# Connections.net
KiCad netlist of a schematic drawn in Altium Designer
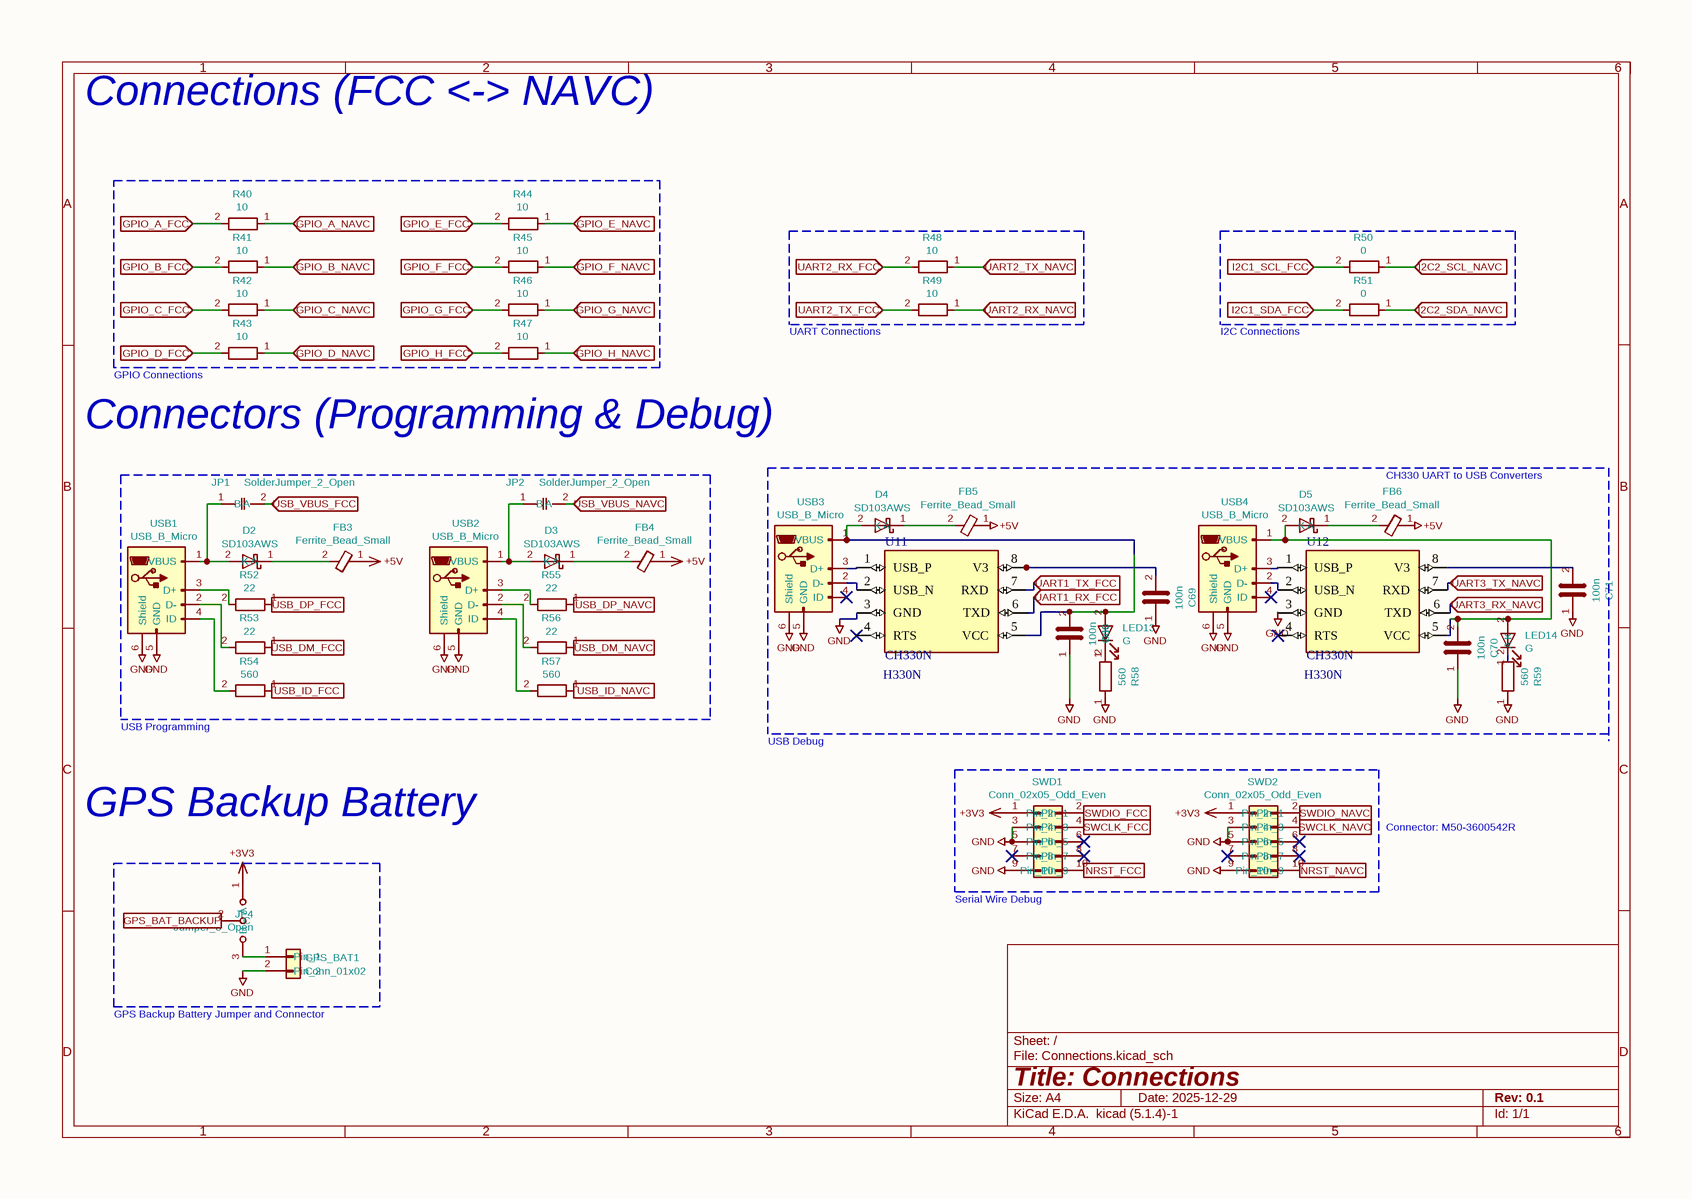
[diagram p0: Connections.SchDoc]

(export (version "E")
  (design (tool "Eeschema 10.0.6"))
  (components
    (comp (ref "C68") (value "100n") (footprint "C_0402_1005Metric") (libsource (lib "Device") (part "C")))
    (comp (ref "C69") (value "100n") (footprint "C_0402_1005Metric") (libsource (lib "Device") (part "C")))
    (comp (ref "C70") (value "100n") (footprint "C_0402_1005Metric") (libsource (lib "Device") (part "C")))
    (comp (ref "C71") (value "100n") (footprint "C_0402_1005Metric") (libsource (lib "Device") (part "C")))
    (comp (ref "D2")
      (value "SD103AWS")
      (footprint "D_SOD-323")
      (libsource (lib "Device") (part "D_Schottky"))
    )
    (comp (ref "D3")
      (value "SD103AWS")
      (footprint "D_SOD-323")
      (libsource (lib "Device") (part "D_Schottky"))
    )
    (comp (ref "D4")
      (value "SD103AWS")
      (footprint "D_SOD-323")
      (libsource (lib "Device") (part "D_Schottky"))
    )
    (comp (ref "D5")
      (value "SD103AWS")
      (footprint "D_SOD-323")
      (libsource (lib "Device") (part "D_Schottky"))
    )
    (comp (ref "FB3")
      (value "Ferrite_Bead_Small")
      (footprint "L_0402_1005Metric")
      (libsource (lib "Hades-rescue") (part "Ferrite_Bead_Small-Device"))
    )
    (comp (ref "FB4")
      (value "Ferrite_Bead_Small")
      (footprint "L_0402_1005Metric")
      (libsource (lib "Hades-rescue") (part "Ferrite_Bead_Small-Device"))
    )
    (comp (ref "FB5")
      (value "Ferrite_Bead_Small")
      (footprint "L_0402_1005Metric")
      (libsource (lib "Hades-rescue") (part "Ferrite_Bead_Small-Device"))
    )
    (comp (ref "FB6")
      (value "Ferrite_Bead_Small")
      (footprint "L_0402_1005Metric")
      (libsource (lib "Hades-rescue") (part "Ferrite_Bead_Small-Device"))
    )
    (comp (ref "GPS_BAT1")
      (value "Conn_01x02")
      (footprint "Molex_PicoBlade_53048-0210_1x02_P1.25mm_Horizontal")
      (libsource (lib "Connector_Generic") (part "Conn_01x02"))
    )
    (comp (ref "JP1")
      (value "SolderJumper_2_Open")
      (footprint "SolderJumper-2_P1.3mm_Open_RoundedPad1.0x1.5mm")
      (libsource (lib "Jumper") (part "SolderJumper_2_Open"))
    )
    (comp (ref "JP2")
      (value "SolderJumper_2_Open")
      (footprint "SolderJumper-2_P1.3mm_Open_RoundedPad1.0x1.5mm")
      (libsource (lib "Jumper") (part "SolderJumper_2_Open"))
    )
    (comp (ref "JP4")
      (value "Jumper_3_Open")
      (footprint "SolderJumper-3_P1.3mm_Open_RoundedPad1.0x1.5mm")
      (libsource (lib "Hades-rescue") (part "Jumper_3_Open-Jumper"))
    )
    (comp (ref "LED13") (value "G") (footprint "LED_0603_1608Metric") (libsource (lib "Device") (part "LED")))
    (comp (ref "LED14") (value "G") (footprint "LED_0603_1608Metric") (libsource (lib "Device") (part "LED")))
    (comp (ref "R40") (value "10") (footprint "R_0402_1005Metric") (libsource (lib "Device") (part "R")))
    (comp (ref "R41") (value "10") (footprint "R_0402_1005Metric") (libsource (lib "Device") (part "R")))
    (comp (ref "R42") (value "10") (footprint "R_0402_1005Metric") (libsource (lib "Device") (part "R")))
    (comp (ref "R43") (value "10") (footprint "R_0402_1005Metric") (libsource (lib "Device") (part "R")))
    (comp (ref "R44") (value "10") (footprint "R_0402_1005Metric") (libsource (lib "Device") (part "R")))
    (comp (ref "R45") (value "10") (footprint "R_0402_1005Metric") (libsource (lib "Device") (part "R")))
    (comp (ref "R46") (value "10") (footprint "R_0402_1005Metric") (libsource (lib "Device") (part "R")))
    (comp (ref "R47") (value "10") (footprint "R_0402_1005Metric") (libsource (lib "Device") (part "R")))
    (comp (ref "R48") (value "10") (footprint "R_0402_1005Metric") (libsource (lib "Device") (part "R")))
    (comp (ref "R49") (value "10") (footprint "R_0402_1005Metric") (libsource (lib "Device") (part "R")))
    (comp (ref "R50") (value "0") (footprint "R_0603_1608Metric") (libsource (lib "Device") (part "R")))
    (comp (ref "R51") (value "0") (footprint "R_0603_1608Metric") (libsource (lib "Device") (part "R")))
    (comp (ref "R52") (value "22") (footprint "R_0402_1005Metric") (libsource (lib "Device") (part "R")))
    (comp (ref "R53") (value "22") (footprint "R_0402_1005Metric") (libsource (lib "Device") (part "R")))
    (comp (ref "R54") (value "560") (footprint "R_0402_1005Metric") (libsource (lib "Device") (part "R")))
    (comp (ref "R55") (value "22") (footprint "R_0402_1005Metric") (libsource (lib "Device") (part "R")))
    (comp (ref "R56") (value "22") (footprint "R_0402_1005Metric") (libsource (lib "Device") (part "R")))
    (comp (ref "R57") (value "560") (footprint "R_0402_1005Metric") (libsource (lib "Device") (part "R")))
    (comp (ref "R58") (value "560") (footprint "R_0603_1608Metric") (libsource (lib "") (part "R_1")))
    (comp (ref "R59") (value "560") (footprint "R_0603_1608Metric") (libsource (lib "") (part "R_1")))
    (comp (ref "SWD1")
      (value "Conn_02x05_Odd_Even")
      (footprint "PinHeader_2x05_P1.27mm_Vertical_SMD")
      (libsource (lib "Connector_Generic") (part "Conn_02x05_Odd_Even"))
    )
    (comp (ref "SWD2")
      (value "Conn_02x05_Odd_Even")
      (footprint "PinHeader_2x05_P1.27mm_Vertical_SMD")
      (libsource (lib "Connector_Generic") (part "Conn_02x05_Odd_Even"))
    )
    (comp (ref "U11")
      (value "H330N")
      (footprint "8-SOIC")
      (description "USB To Serial Chip")
      (fields (field (name "MP") "CH330N") (field (name "MF") "WCH"))
      (libsource (lib "CH330N") (part "CH330N"))
    )
    (comp (ref "U12")
      (value "H330N")
      (footprint "8-SOIC")
      (description "USB To Serial Chip")
      (fields (field (name "MP") "CH330N") (field (name "MF") "WCH"))
      (libsource (lib "CH330N") (part "CH330N"))
    )
    (comp (ref "USB1")
      (value "USB_B_Micro")
      (footprint "USB_Micro-B_Wuerth_629105150521_CircularHoles")
      (libsource (lib "Hades-rescue") (part "USB_B_Micro-Connector"))
    )
    (comp (ref "USB2")
      (value "USB_B_Micro")
      (footprint "USB_Micro-B_Wuerth_629105150521_CircularHoles")
      (libsource (lib "Hades-rescue") (part "USB_B_Micro-Connector"))
    )
    (comp (ref "USB3")
      (value "USB_B_Micro")
      (footprint "USB_Micro-B_Wuerth_629105150521_CircularHoles")
      (libsource (lib "Hades-rescue") (part "USB_B_Micro-Connector"))
    )
    (comp (ref "USB4")
      (value "USB_B_Micro")
      (footprint "USB_Micro-B_Wuerth_629105150521_CircularHoles")
      (libsource (lib "Hades-rescue") (part "USB_B_Micro-Connector"))
    )
  )
  (nets
    (net (code "1") (name "+3V3") (class "Default")
      (node (ref "JP4") (pin "1") (pinfunction "A_1") (pintype "passive"))
      (node (ref "SWD1") (pin "1") (pinfunction "Pin_1_1") (pintype "passive"))
      (node (ref "SWD2") (pin "1") (pinfunction "Pin_1_1") (pintype "passive"))
    )
    (net (code "2") (name "+5V") (class "Default")
      (node (ref "FB3") (pin "1") (pinfunction "1_1") (pintype "passive"))
      (node (ref "FB4") (pin "1") (pinfunction "1_1") (pintype "passive"))
      (node (ref "FB5") (pin "1") (pinfunction "1_1") (pintype "passive"))
      (node (ref "FB6") (pin "1") (pinfunction "1_1") (pintype "passive"))
    )
    (net (code "3") (name "/GPIO_A_FCC") (class "Default")
      (node (ref "R40") (pin "2") (pinfunction "2_2") (pintype "passive"))
    )
    (net (code "4") (name "/GPIO_A_NAVC") (class "Default")
      (node (ref "R40") (pin "1") (pinfunction "1_1") (pintype "passive"))
    )
    (net (code "5") (name "/GPIO_B_FCC") (class "Default")
      (node (ref "R41") (pin "2") (pinfunction "2_2") (pintype "passive"))
    )
    (net (code "6") (name "/GPIO_B_NAVC") (class "Default")
      (node (ref "R41") (pin "1") (pinfunction "1_1") (pintype "passive"))
    )
    (net (code "7") (name "/GPIO_C_FCC") (class "Default")
      (node (ref "R42") (pin "2") (pinfunction "2_2") (pintype "passive"))
    )
    (net (code "8") (name "/GPIO_C_NAVC") (class "Default")
      (node (ref "R42") (pin "1") (pinfunction "1_1") (pintype "passive"))
    )
    (net (code "9") (name "/GPIO_D_FCC") (class "Default")
      (node (ref "R43") (pin "2") (pinfunction "2_2") (pintype "passive"))
    )
    (net (code "10") (name "/GPIO_D_NAVC") (class "Default")
      (node (ref "R43") (pin "1") (pinfunction "1_1") (pintype "passive"))
    )
    (net (code "11") (name "/GPIO_E_FCC") (class "Default")
      (node (ref "R44") (pin "2") (pinfunction "2_2") (pintype "passive"))
    )
    (net (code "12") (name "/GPIO_E_NAVC") (class "Default")
      (node (ref "R44") (pin "1") (pinfunction "1_1") (pintype "passive"))
    )
    (net (code "13") (name "/GPIO_F_FCC") (class "Default")
      (node (ref "R45") (pin "2") (pinfunction "2_2") (pintype "passive"))
    )
    (net (code "14") (name "/GPIO_F_NAVC") (class "Default")
      (node (ref "R45") (pin "1") (pinfunction "1_1") (pintype "passive"))
    )
    (net (code "15") (name "/GPIO_G_FCC") (class "Default")
      (node (ref "R46") (pin "2") (pinfunction "2_2") (pintype "passive"))
    )
    (net (code "16") (name "/GPIO_G_NAVC") (class "Default")
      (node (ref "R46") (pin "1") (pinfunction "1_1") (pintype "passive"))
    )
    (net (code "17") (name "/GPIO_H_FCC") (class "Default")
      (node (ref "R47") (pin "2") (pinfunction "2_2") (pintype "passive"))
    )
    (net (code "18") (name "/GPIO_H_NAVC") (class "Default")
      (node (ref "R47") (pin "1") (pinfunction "1_1") (pintype "passive"))
    )
    (net (code "19") (name "/GPS_BAT_BACKUP") (class "Default")
      (node (ref "JP4") (pin "2") (pinfunction "C_2") (pintype "passive"))
    )
    (net (code "20") (name "/I2C1_SCL_FCC") (class "Default")
      (node (ref "R50") (pin "2") (pinfunction "2_2") (pintype "passive"))
    )
    (net (code "21") (name "/I2C1_SDA_FCC") (class "Default")
      (node (ref "R51") (pin "2") (pinfunction "2_2") (pintype "passive"))
    )
    (net (code "22") (name "/I2C2_SCL_NAVC") (class "Default")
      (node (ref "R50") (pin "1") (pinfunction "1_1") (pintype "passive"))
    )
    (net (code "23") (name "/I2C2_SDA_NAVC") (class "Default")
      (node (ref "R51") (pin "1") (pinfunction "1_1") (pintype "passive"))
    )
    (net (code "24") (name "/NRST_FCC") (class "Default")
      (node (ref "SWD1") (pin "10") (pinfunction "Pin_10_10") (pintype "passive"))
    )
    (net (code "25") (name "/NRST_NAVC") (class "Default")
      (node (ref "SWD2") (pin "10") (pinfunction "Pin_10_10") (pintype "passive"))
    )
    (net (code "26") (name "/SWCLK_FCC") (class "Default")
      (node (ref "SWD1") (pin "4") (pinfunction "Pin_4_4") (pintype "passive"))
    )
    (net (code "27") (name "/SWCLK_NAVC") (class "Default")
      (node (ref "SWD2") (pin "4") (pinfunction "Pin_4_4") (pintype "passive"))
    )
    (net (code "28") (name "/SWDIO_FCC") (class "Default")
      (node (ref "SWD1") (pin "2") (pinfunction "Pin_2_2") (pintype "passive"))
    )
    (net (code "29") (name "/SWDIO_NAVC") (class "Default")
      (node (ref "SWD2") (pin "2") (pinfunction "Pin_2_2") (pintype "passive"))
    )
    (net (code "30") (name "/UART1_RX_FCC") (class "Default")
      (node (ref "U11") (pin "6") (pinfunction "TXD_6") (pintype "bidirectional"))
    )
    (net (code "31") (name "/UART1_TX_FCC") (class "Default")
      (node (ref "U11") (pin "7") (pinfunction "RXD_7") (pintype "bidirectional"))
    )
    (net (code "32") (name "/UART2_RX_FCC") (class "Default")
      (node (ref "R48") (pin "2") (pinfunction "2_2") (pintype "passive"))
    )
    (net (code "33") (name "/UART2_RX_NAVC") (class "Default")
      (node (ref "R49") (pin "1") (pinfunction "1_1") (pintype "passive"))
    )
    (net (code "34") (name "/UART2_TX_FCC") (class "Default")
      (node (ref "R49") (pin "2") (pinfunction "2_2") (pintype "passive"))
    )
    (net (code "35") (name "/UART2_TX_NAVC") (class "Default")
      (node (ref "R48") (pin "1") (pinfunction "1_1") (pintype "passive"))
    )
    (net (code "36") (name "/UART3_RX_NAVC") (class "Default")
      (node (ref "U12") (pin "6") (pinfunction "TXD_6") (pintype "bidirectional"))
    )
    (net (code "37") (name "/UART3_TX_NAVC") (class "Default")
      (node (ref "U12") (pin "7") (pinfunction "RXD_7") (pintype "bidirectional"))
    )
    (net (code "38") (name "/USB_DM_FCC") (class "Default")
      (node (ref "R53") (pin "1") (pinfunction "1_1") (pintype "passive"))
    )
    (net (code "39") (name "/USB_DM_NAVC") (class "Default")
      (node (ref "R56") (pin "1") (pinfunction "1_1") (pintype "passive"))
    )
    (net (code "40") (name "/USB_DP_FCC") (class "Default")
      (node (ref "R52") (pin "1") (pinfunction "1_1") (pintype "passive"))
    )
    (net (code "41") (name "/USB_DP_NAVC") (class "Default")
      (node (ref "R55") (pin "1") (pinfunction "1_1") (pintype "passive"))
    )
    (net (code "42") (name "/USB_ID_FCC") (class "Default")
      (node (ref "R54") (pin "1") (pinfunction "1_1") (pintype "passive"))
    )
    (net (code "43") (name "/USB_ID_NAVC") (class "Default")
      (node (ref "R57") (pin "1") (pinfunction "1_1") (pintype "passive"))
    )
    (net (code "44") (name "/USB_VBUS_FCC") (class "Default")
      (node (ref "JP1") (pin "2") (pinfunction "B_2") (pintype "passive"))
    )
    (net (code "45") (name "/USB_VBUS_NAVC") (class "Default")
      (node (ref "JP2") (pin "2") (pinfunction "B_2") (pintype "passive"))
    )
    (net (code "46") (name "GND") (class "Default")
      (node (ref "C68") (pin "1") (pinfunction "1_1") (pintype "passive"))
      (node (ref "C69") (pin "1") (pinfunction "1_1") (pintype "passive"))
      (node (ref "C70") (pin "1") (pinfunction "1_1") (pintype "passive"))
      (node (ref "C71") (pin "1") (pinfunction "1_1") (pintype "passive"))
      (node (ref "GPS_BAT1") (pin "2") (pinfunction "Pin_2_2") (pintype "passive"))
      (node (ref "R58") (pin "1") (pinfunction "1_1") (pintype "passive"))
      (node (ref "R59") (pin "1") (pinfunction "1_1") (pintype "passive"))
      (node (ref "SWD1") (pin "3") (pinfunction "Pin_3_3") (pintype "passive"))
      (node (ref "SWD1") (pin "5") (pinfunction "Pin_5_5") (pintype "passive"))
      (node (ref "SWD1") (pin "9") (pinfunction "Pin_9_9") (pintype "passive"))
      (node (ref "SWD2") (pin "3") (pinfunction "Pin_3_3") (pintype "passive"))
      (node (ref "SWD2") (pin "5") (pinfunction "Pin_5_5") (pintype "passive"))
      (node (ref "SWD2") (pin "9") (pinfunction "Pin_9_9") (pintype "passive"))
      (node (ref "U11") (pin "3") (pinfunction "GND_3") (pintype "bidirectional"))
      (node (ref "USB1") (pin "5") (pinfunction "GND_5") (pintype "passive"))
      (node (ref "USB1") (pin "6") (pinfunction "Shield_6") (pintype "passive"))
      (node (ref "USB2") (pin "5") (pinfunction "GND_5") (pintype "passive"))
      (node (ref "USB2") (pin "6") (pinfunction "Shield_6") (pintype "passive"))
      (node (ref "USB3") (pin "5") (pinfunction "GND_5") (pintype "passive"))
      (node (ref "USB3") (pin "6") (pinfunction "Shield_6") (pintype "passive"))
      (node (ref "USB4") (pin "5") (pinfunction "GND_5") (pintype "passive"))
      (node (ref "USB4") (pin "6") (pinfunction "Shield_6") (pintype "passive"))
    )
    (net (code "47") (name "Net-(D2-A)") (class "Default")
      (node (ref "D2") (pin "2") (pinfunction "A_2") (pintype "passive"))
      (node (ref "JP1") (pin "1") (pinfunction "A_1") (pintype "passive"))
      (node (ref "USB1") (pin "1") (pinfunction "VBUS_1") (pintype "passive"))
    )
    (net (code "48") (name "Net-(D2-K)") (class "Default")
      (node (ref "D2") (pin "1") (pinfunction "K_1") (pintype "passive"))
      (node (ref "FB3") (pin "2") (pinfunction "2_2") (pintype "passive"))
    )
    (net (code "49") (name "Net-(D3-A)") (class "Default")
      (node (ref "D3") (pin "2") (pinfunction "A_2") (pintype "passive"))
      (node (ref "JP2") (pin "1") (pinfunction "A_1") (pintype "passive"))
      (node (ref "USB2") (pin "1") (pinfunction "VBUS_1") (pintype "passive"))
    )
    (net (code "50") (name "Net-(D3-K)") (class "Default")
      (node (ref "D3") (pin "1") (pinfunction "K_1") (pintype "passive"))
      (node (ref "FB4") (pin "2") (pinfunction "2_2") (pintype "passive"))
    )
    (net (code "51") (name "Net-(D4-A)") (class "Default")
      (node (ref "C68") (pin "2") (pinfunction "2_2") (pintype "passive"))
      (node (ref "D4") (pin "2") (pinfunction "A_2") (pintype "passive"))
      (node (ref "LED13") (pin "2") (pinfunction "A_2") (pintype "passive"))
      (node (ref "U11") (pin "5") (pinfunction "VCC_5") (pintype "bidirectional"))
      (node (ref "USB3") (pin "1") (pinfunction "VBUS_1") (pintype "passive"))
    )
    (net (code "52") (name "Net-(D4-K)") (class "Default")
      (node (ref "D4") (pin "1") (pinfunction "K_1") (pintype "passive"))
      (node (ref "FB5") (pin "2") (pinfunction "2_2") (pintype "passive"))
    )
    (net (code "53") (name "Net-(D5-A)") (class "Default")
      (node (ref "C70") (pin "2") (pinfunction "2_2") (pintype "passive"))
      (node (ref "D5") (pin "2") (pinfunction "A_2") (pintype "passive"))
      (node (ref "LED14") (pin "2") (pinfunction "A_2") (pintype "passive"))
      (node (ref "U12") (pin "5") (pinfunction "VCC_5") (pintype "bidirectional"))
      (node (ref "USB4") (pin "1") (pinfunction "VBUS_1") (pintype "passive"))
    )
    (net (code "54") (name "Net-(D5-K)") (class "Default")
      (node (ref "D5") (pin "1") (pinfunction "K_1") (pintype "passive"))
      (node (ref "FB6") (pin "2") (pinfunction "2_2") (pintype "passive"))
    )
    (net (code "55") (name "Net-(GPS_BAT1-Pin_1)") (class "Default")
      (node (ref "GPS_BAT1") (pin "1") (pinfunction "Pin_1_1") (pintype "passive"))
      (node (ref "JP4") (pin "3") (pinfunction "B_3") (pintype "passive"))
    )
    (net (code "56") (name "Net-(LED13-K)") (class "Default")
      (node (ref "LED13") (pin "1") (pinfunction "K_1") (pintype "passive"))
      (node (ref "R58") (pin "2") (pinfunction "2_2") (pintype "passive"))
    )
    (net (code "57") (name "Net-(LED14-K)") (class "Default")
      (node (ref "LED14") (pin "1") (pinfunction "K_1") (pintype "passive"))
      (node (ref "R59") (pin "2") (pinfunction "2_2") (pintype "passive"))
    )
    (net (code "58") (name "Net-(U11-USB_N)") (class "Default")
      (node (ref "U11") (pin "2") (pinfunction "USB_N_2") (pintype "bidirectional"))
      (node (ref "USB3") (pin "2") (pinfunction "D-_2") (pintype "passive"))
    )
    (net (code "59") (name "Net-(U11-USB_P)") (class "Default")
      (node (ref "U11") (pin "1") (pinfunction "USB_P_1") (pintype "bidirectional"))
      (node (ref "USB3") (pin "3") (pinfunction "D+_3") (pintype "passive"))
    )
    (net (code "60") (name "Net-(U11-V3)") (class "Default")
      (node (ref "C69") (pin "2") (pinfunction "2_2") (pintype "passive"))
      (node (ref "U11") (pin "8") (pinfunction "V3_8") (pintype "bidirectional"))
    )
    (net (code "61") (name "Net-(U12-USB_N)") (class "Default")
      (node (ref "U12") (pin "2") (pinfunction "USB_N_2") (pintype "bidirectional"))
      (node (ref "USB4") (pin "2") (pinfunction "D-_2") (pintype "passive"))
    )
    (net (code "62") (name "Net-(U12-USB_P)") (class "Default")
      (node (ref "U12") (pin "1") (pinfunction "USB_P_1") (pintype "bidirectional"))
      (node (ref "USB4") (pin "3") (pinfunction "D+_3") (pintype "passive"))
    )
    (net (code "63") (name "Net-(U12-V3)") (class "Default")
      (node (ref "C71") (pin "2") (pinfunction "2_2") (pintype "passive"))
      (node (ref "U12") (pin "8") (pinfunction "V3_8") (pintype "bidirectional"))
    )
    (net (code "64") (name "Net-(USB1-D+)") (class "Default")
      (node (ref "R52") (pin "2") (pinfunction "2_2") (pintype "passive"))
      (node (ref "USB1") (pin "3") (pinfunction "D+_3") (pintype "passive"))
    )
    (net (code "65") (name "Net-(USB1-D-)") (class "Default")
      (node (ref "R53") (pin "2") (pinfunction "2_2") (pintype "passive"))
      (node (ref "USB1") (pin "2") (pinfunction "D-_2") (pintype "passive"))
    )
    (net (code "66") (name "Net-(USB1-ID)") (class "Default")
      (node (ref "R54") (pin "2") (pinfunction "2_2") (pintype "passive"))
      (node (ref "USB1") (pin "4") (pinfunction "ID_4") (pintype "passive"))
    )
    (net (code "67") (name "Net-(USB2-D+)") (class "Default")
      (node (ref "R55") (pin "2") (pinfunction "2_2") (pintype "passive"))
      (node (ref "USB2") (pin "3") (pinfunction "D+_3") (pintype "passive"))
    )
    (net (code "68") (name "Net-(USB2-D-)") (class "Default")
      (node (ref "R56") (pin "2") (pinfunction "2_2") (pintype "passive"))
      (node (ref "USB2") (pin "2") (pinfunction "D-_2") (pintype "passive"))
    )
    (net (code "69") (name "Net-(USB2-ID)") (class "Default")
      (node (ref "R57") (pin "2") (pinfunction "2_2") (pintype "passive"))
      (node (ref "USB2") (pin "4") (pinfunction "ID_4") (pintype "passive"))
    )
    (net (code "70") (name "unconnected-(SWD1-Pin_6-Pad6)") (class "Default")
      (node (ref "SWD1") (pin "6") (pinfunction "Pin_6_6") (pintype "passive+no_connect"))
    )
    (net (code "71") (name "unconnected-(SWD1-Pin_7-Pad7)") (class "Default")
      (node (ref "SWD1") (pin "7") (pinfunction "Pin_7_7") (pintype "passive+no_connect"))
    )
    (net (code "72") (name "unconnected-(SWD1-Pin_8-Pad8)") (class "Default")
      (node (ref "SWD1") (pin "8") (pinfunction "Pin_8_8") (pintype "passive+no_connect"))
    )
    (net (code "73") (name "unconnected-(SWD2-Pin_6-Pad6)") (class "Default")
      (node (ref "SWD2") (pin "6") (pinfunction "Pin_6_6") (pintype "passive+no_connect"))
    )
    (net (code "74") (name "unconnected-(SWD2-Pin_7-Pad7)") (class "Default")
      (node (ref "SWD2") (pin "7") (pinfunction "Pin_7_7") (pintype "passive+no_connect"))
    )
    (net (code "75") (name "unconnected-(SWD2-Pin_8-Pad8)") (class "Default")
      (node (ref "SWD2") (pin "8") (pinfunction "Pin_8_8") (pintype "passive+no_connect"))
    )
    (net (code "76") (name "unconnected-(U11-RTS-Pad4)") (class "Default")
      (node (ref "U11") (pin "4") (pinfunction "RTS_4") (pintype "bidirectional+no_connect"))
    )
    (net (code "77") (name "unconnected-(U12-GND-Pad3)") (class "Default")
      (node (ref "U12") (pin "3") (pinfunction "GND_3") (pintype "bidirectional"))
    )
    (net (code "78") (name "unconnected-(U12-RTS-Pad4)") (class "Default")
      (node (ref "U12") (pin "4") (pinfunction "RTS_4") (pintype "bidirectional+no_connect"))
    )
    (net (code "79") (name "unconnected-(USB3-ID-Pad4)") (class "Default")
      (node (ref "USB3") (pin "4") (pinfunction "ID_4") (pintype "passive+no_connect"))
    )
    (net (code "80") (name "unconnected-(USB4-ID-Pad4)") (class "Default")
      (node (ref "USB4") (pin "4") (pinfunction "ID_4") (pintype "passive+no_connect"))
    )
  )
)
